# pedal_pre.net
KiCad netlist of a schematic drawn in EAGLE
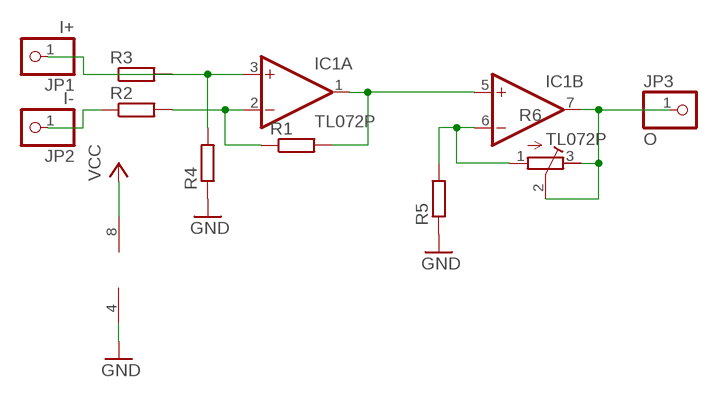
[diagram p0: schematic, sheet 1]

(export (version "E")
  (design (tool "Eeschema 10.0.6"))
  (components
    (comp (ref "IC1")
      (value "TL072P")
      (footprint "eagle-import:DIL08")
      (libsource (lib "eagle-import") (part "TL072P"))
    )
    (comp (ref "JP1")
      (value "I+")
      (footprint "eagle-import:1X01")
      (libsource (lib "eagle-import") (part "PINHD-1X1"))
    )
    (comp (ref "JP2")
      (value "I-")
      (footprint "eagle-import:1X01")
      (libsource (lib "eagle-import") (part "PINHD-1X1"))
    )
    (comp (ref "JP3")
      (value "O")
      (footprint "eagle-import:1X01")
      (libsource (lib "eagle-import") (part "PINHD-1X1"))
    )
    (comp (ref "R1")
      (value "R-EU_0207/2V")
      (footprint "eagle-import:0207_2V")
      (libsource (lib "eagle-import") (part "R-EU_0207/2V"))
    )
    (comp (ref "R2")
      (value "R-EU_0207/2V")
      (footprint "eagle-import:0207_2V")
      (libsource (lib "eagle-import") (part "R-EU_0207/2V"))
    )
    (comp (ref "R3")
      (value "R-EU_0207/2V")
      (footprint "eagle-import:0207_2V")
      (libsource (lib "eagle-import") (part "R-EU_0207/2V"))
    )
    (comp (ref "R4")
      (value "R-EU_0207/2V")
      (footprint "eagle-import:0207_2V")
      (libsource (lib "eagle-import") (part "R-EU_0207/2V"))
    )
    (comp (ref "R5")
      (value "R-EU_0207/2V")
      (footprint "eagle-import:0207_2V")
      (libsource (lib "eagle-import") (part "R-EU_0207/2V"))
    )
    (comp (ref "R6")
      (value "R-TRIMM64W")
      (footprint "eagle-import:RTRIM64W")
      (libsource (lib "eagle-import") (part "R-TRIMM64W"))
    )
  )
  (nets
    (net (code "1") (name "GND") (class "Default")
      (node (ref "IC1") (pin "4") (pinfunction "V-_4") (pintype "power_in"))
      (node (ref "R4") (pin "1") (pinfunction "1_1") (pintype "passive"))
      (node (ref "R5") (pin "1") (pinfunction "1_1") (pintype "passive"))
    )
    (net (code "2") (name "Net-(IC1A-+IN)") (class "Default")
      (node (ref "IC1") (pin "3") (pinfunction "+IN_3") (pintype "input"))
      (node (ref "R3") (pin "1") (pinfunction "1_1") (pintype "passive"))
      (node (ref "R4") (pin "2") (pinfunction "2_2") (pintype "passive"))
    )
    (net (code "3") (name "Net-(IC1A--IN)") (class "Default")
      (node (ref "IC1") (pin "2") (pinfunction "-IN_2") (pintype "input"))
      (node (ref "R1") (pin "1") (pinfunction "1_1") (pintype "passive"))
      (node (ref "R2") (pin "2") (pinfunction "2_2") (pintype "passive"))
    )
    (net (code "4") (name "Net-(IC1A-OUT)") (class "Default")
      (node (ref "IC1") (pin "1") (pinfunction "OUT_1") (pintype "output"))
      (node (ref "IC1") (pin "5") (pinfunction "+IN_5") (pintype "input"))
      (node (ref "R1") (pin "2") (pinfunction "2_2") (pintype "passive"))
    )
    (net (code "5") (name "Net-(IC1B--IN)") (class "Default")
      (node (ref "IC1") (pin "6") (pinfunction "-IN_6") (pintype "input"))
      (node (ref "R5") (pin "2") (pinfunction "2_2") (pintype "passive"))
      (node (ref "R6") (pin "1") (pinfunction "A_1") (pintype "passive"))
    )
    (net (code "6") (name "Net-(IC1B-OUT)") (class "Default")
      (node (ref "IC1") (pin "7") (pinfunction "OUT_7") (pintype "output"))
      (node (ref "JP3") (pin "1") (pinfunction "1_1") (pintype "passive"))
      (node (ref "R6") (pin "2") (pinfunction "S_2") (pintype "passive"))
      (node (ref "R6") (pin "3") (pinfunction "E_3") (pintype "passive"))
    )
    (net (code "7") (name "Net-(JP1-Pad1)") (class "Default")
      (node (ref "JP1") (pin "1") (pinfunction "1_1") (pintype "passive"))
      (node (ref "R3") (pin "2") (pinfunction "2_2") (pintype "passive"))
    )
    (net (code "8") (name "Net-(JP2-Pad1)") (class "Default")
      (node (ref "JP2") (pin "1") (pinfunction "1_1") (pintype "passive"))
      (node (ref "R2") (pin "1") (pinfunction "1_1") (pintype "passive"))
    )
    (net (code "9") (name "VCC") (class "Default")
      (node (ref "IC1") (pin "8") (pinfunction "V+_8") (pintype "power_in"))
    )
  )
)
